# 01_ZYNQ_POWER.net
KiCad netlist of a schematic drawn in Altium Designer
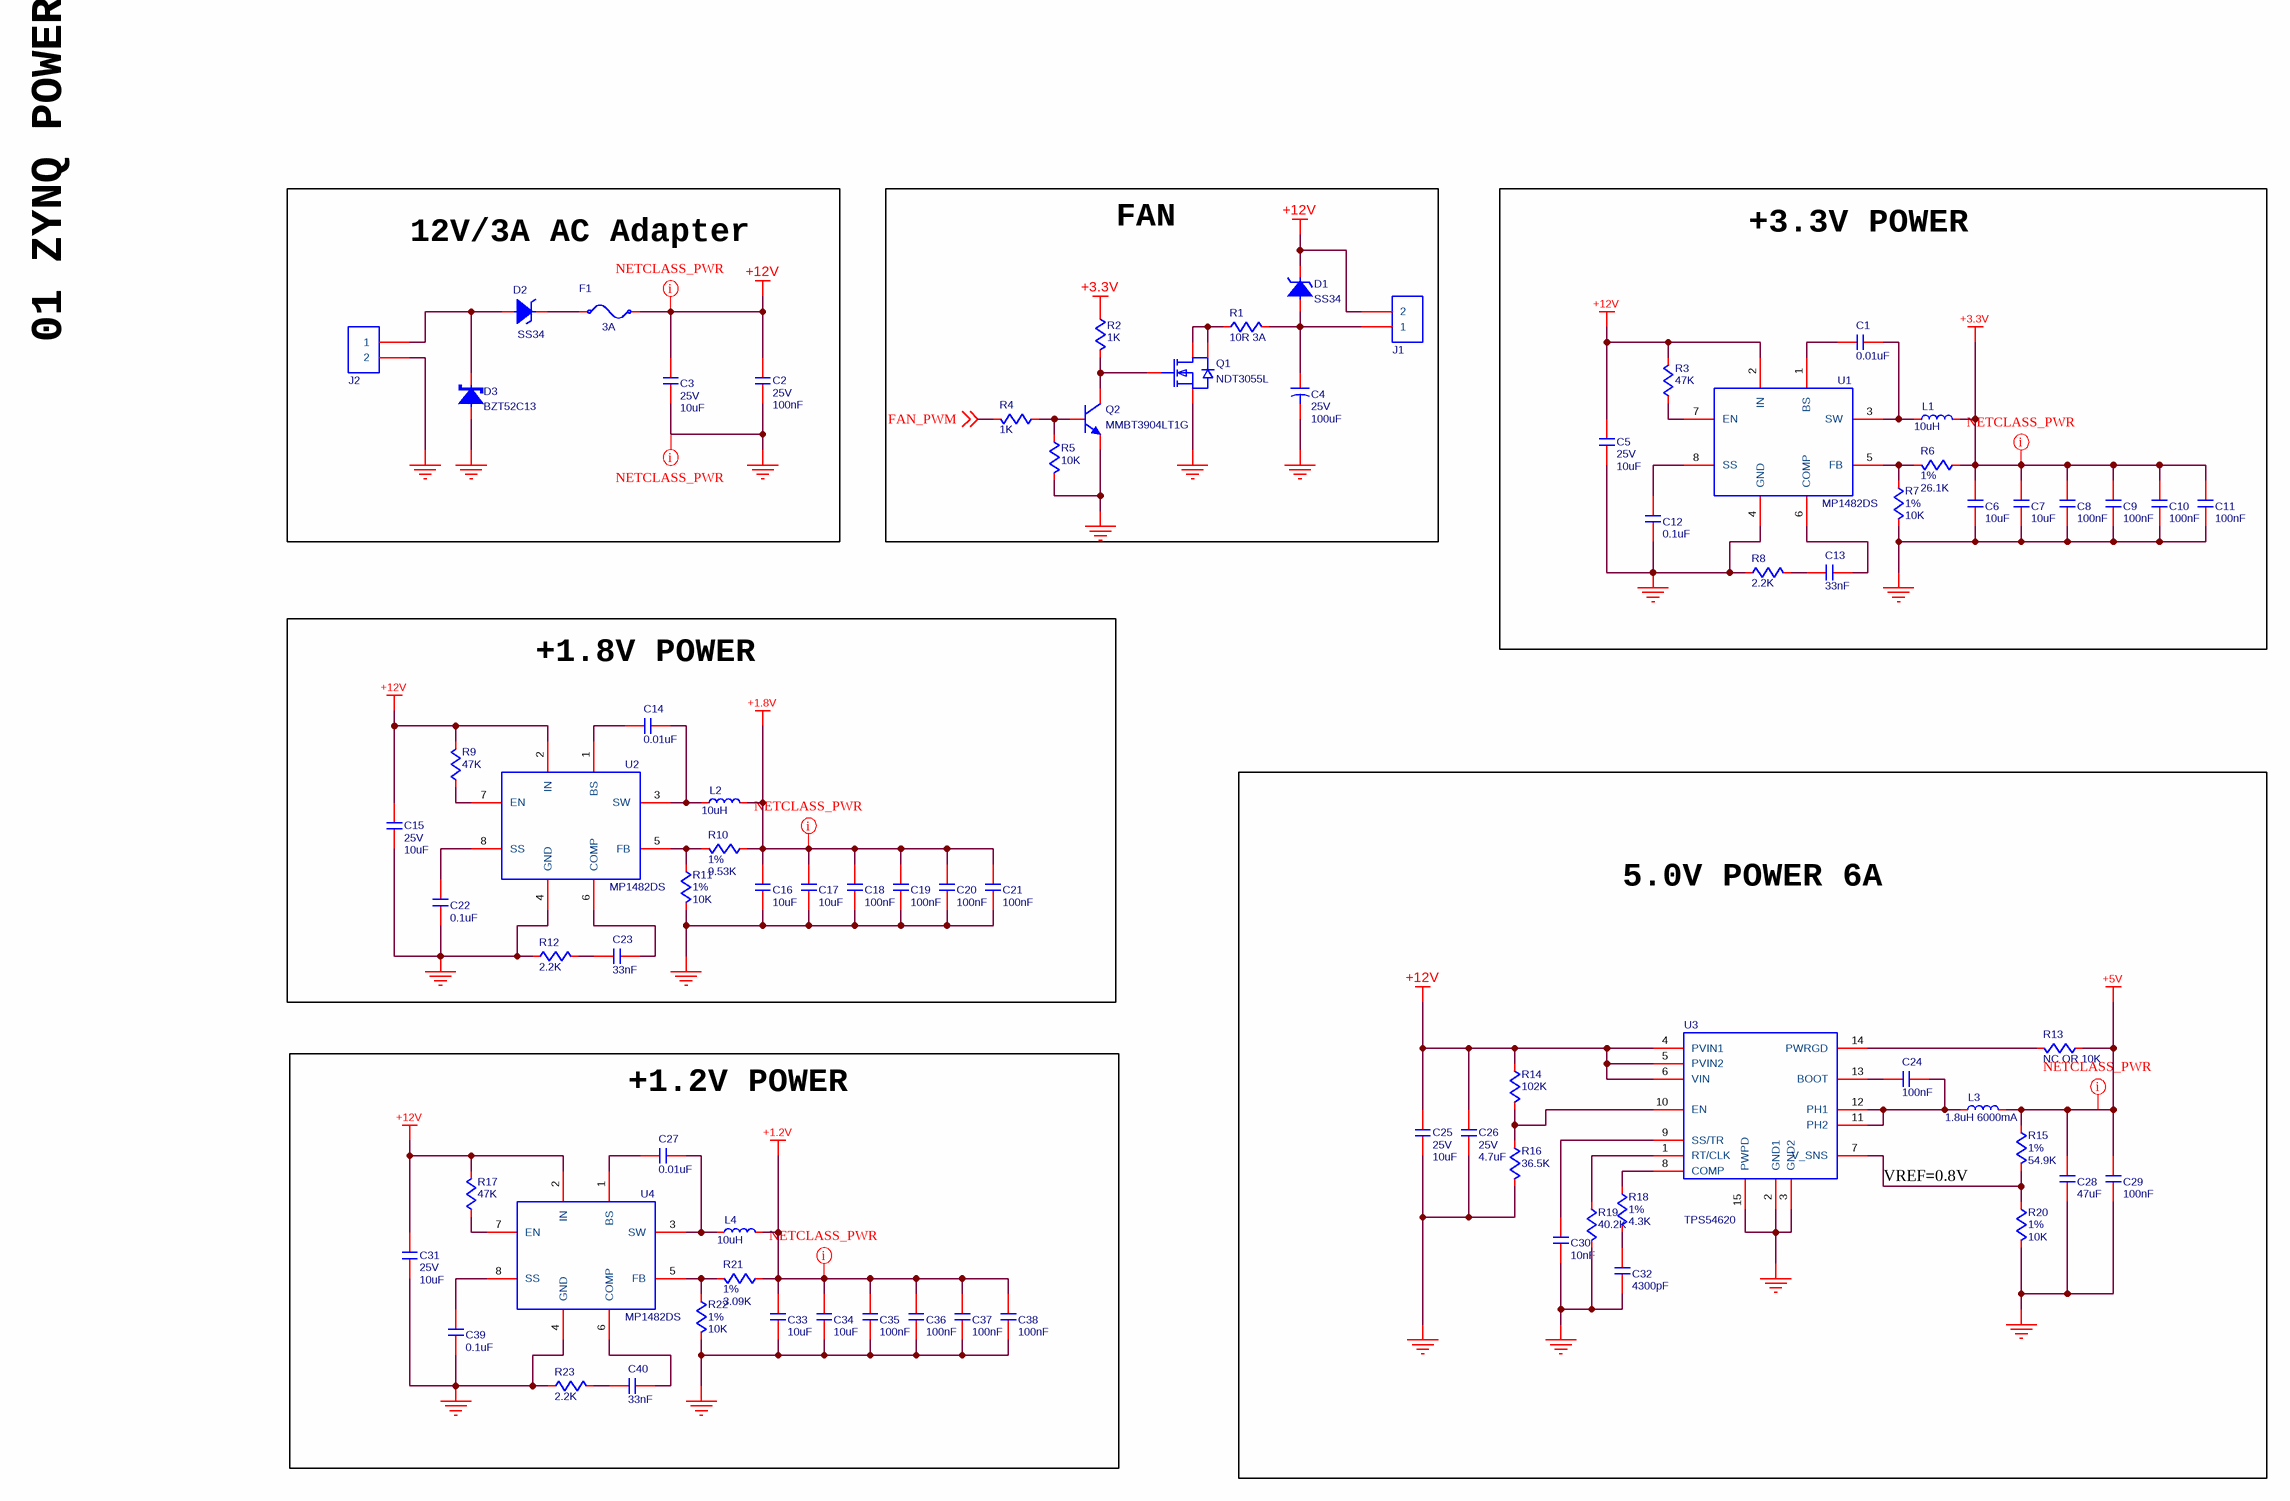
[diagram p0: 01_ZYNQ_POWER.SchDoc]

(export (version "E")
  (design (tool "Eeschema 10.0.6"))
  (components
    (comp (ref "C1")
      (value "0.01uF")
      (footprint "zynq:C0402")
      (fields (field (name "VOLTAGE") "25V") (field (name "Comment") "C-NOMO"))
      (libsource (lib "zynq") (part "C-NOMO"))
    )
    (comp (ref "C2")
      (value "100nF")
      (footprint "zynq:C0402")
      (fields (field (name "VOLTAGE") "25V") (field (name "Comment") "C-NOMO"))
      (libsource (lib "zynq") (part "C-NOMO"))
    )
    (comp (ref "C3")
      (value "10uF")
      (footprint "zynq:C0805")
      (fields (field (name "VOLTAGE") "25V") (field (name "Comment") "C-NOMO"))
      (libsource (lib "zynq") (part "C-NOMO"))
    )
    (comp (ref "C4")
      (value "100uF")
      (footprint "zynq:C7343")
      (fields (field (name "VOLTAGE") "25V") (field (name "Comment") "C-POL"))
      (libsource (lib "zynq") (part "C-POL"))
    )
    (comp (ref "C5")
      (value "10uF")
      (footprint "zynq:C0805")
      (fields (field (name "VOLTAGE") "25V") (field (name "Comment") "C-NOMO"))
      (libsource (lib "zynq") (part "C-NOMO"))
    )
    (comp (ref "C6")
      (value "10uF")
      (footprint "zynq:C0805")
      (fields (field (name "VOLTAGE") "25V") (field (name "Comment") "C-NOMO"))
      (libsource (lib "zynq") (part "C-NOMO"))
    )
    (comp (ref "C7")
      (value "10uF")
      (footprint "zynq:C0805")
      (fields (field (name "VOLTAGE") "25V") (field (name "Comment") "C-NOMO"))
      (libsource (lib "zynq") (part "C-NOMO"))
    )
    (comp (ref "C8")
      (value "100nF")
      (footprint "zynq:C0402")
      (fields (field (name "VOLTAGE") "25V") (field (name "Comment") "C-NOMO"))
      (libsource (lib "zynq") (part "C-NOMO"))
    )
    (comp (ref "C9")
      (value "100nF")
      (footprint "zynq:C0402")
      (fields (field (name "VOLTAGE") "25V") (field (name "Comment") "C-NOMO"))
      (libsource (lib "zynq") (part "C-NOMO"))
    )
    (comp (ref "C10")
      (value "100nF")
      (footprint "zynq:C0402")
      (fields (field (name "VOLTAGE") "25V") (field (name "Comment") "C-NOMO"))
      (libsource (lib "zynq") (part "C-NOMO"))
    )
    (comp (ref "C11")
      (value "100nF")
      (footprint "zynq:C0402")
      (fields (field (name "VOLTAGE") "25V") (field (name "Comment") "C-NOMO"))
      (libsource (lib "zynq") (part "C-NOMO"))
    )
    (comp (ref "C12")
      (value "0.1uF")
      (footprint "zynq:C0402")
      (fields (field (name "VOLTAGE") "25V") (field (name "Comment") "C-NOMO"))
      (libsource (lib "zynq") (part "C-NOMO"))
    )
    (comp (ref "C13")
      (value "33nF")
      (footprint "zynq:C0402")
      (fields (field (name "VOLTAGE") "25V") (field (name "Comment") "C-NOMO"))
      (libsource (lib "zynq") (part "C-NOMO"))
    )
    (comp (ref "C14")
      (value "0.01uF")
      (footprint "zynq:C0402")
      (fields (field (name "VOLTAGE") "25V") (field (name "Comment") "C-NOMO"))
      (libsource (lib "zynq") (part "C-NOMO"))
    )
    (comp (ref "C15")
      (value "10uF")
      (footprint "zynq:C0805")
      (fields (field (name "VOLTAGE") "25V") (field (name "Comment") "C-NOMO"))
      (libsource (lib "zynq") (part "C-NOMO"))
    )
    (comp (ref "C16")
      (value "10uF")
      (footprint "zynq:C0805")
      (fields (field (name "VOLTAGE") "25V") (field (name "Comment") "C-NOMO"))
      (libsource (lib "zynq") (part "C-NOMO"))
    )
    (comp (ref "C17")
      (value "10uF")
      (footprint "zynq:C0805")
      (fields (field (name "VOLTAGE") "25V") (field (name "Comment") "C-NOMO"))
      (libsource (lib "zynq") (part "C-NOMO"))
    )
    (comp (ref "C18")
      (value "100nF")
      (footprint "zynq:C0402")
      (fields (field (name "VOLTAGE") "25V") (field (name "Comment") "C-NOMO"))
      (libsource (lib "zynq") (part "C-NOMO"))
    )
    (comp (ref "C19")
      (value "100nF")
      (footprint "zynq:C0402")
      (fields (field (name "VOLTAGE") "25V") (field (name "Comment") "C-NOMO"))
      (libsource (lib "zynq") (part "C-NOMO"))
    )
    (comp (ref "C20")
      (value "100nF")
      (footprint "zynq:C0402")
      (fields (field (name "VOLTAGE") "25V") (field (name "Comment") "C-NOMO"))
      (libsource (lib "zynq") (part "C-NOMO"))
    )
    (comp (ref "C21")
      (value "100nF")
      (footprint "zynq:C0402")
      (fields (field (name "VOLTAGE") "25V") (field (name "Comment") "C-NOMO"))
      (libsource (lib "zynq") (part "C-NOMO"))
    )
    (comp (ref "C22")
      (value "0.1uF")
      (footprint "zynq:C0402")
      (fields (field (name "VOLTAGE") "25V") (field (name "Comment") "C-NOMO"))
      (libsource (lib "zynq") (part "C-NOMO"))
    )
    (comp (ref "C23")
      (value "33nF")
      (footprint "zynq:C0402")
      (fields (field (name "VOLTAGE") "25V") (field (name "Comment") "C-NOMO"))
      (libsource (lib "zynq") (part "C-NOMO"))
    )
    (comp (ref "C24")
      (value "100nF")
      (footprint "zynq:C0402")
      (fields (field (name "VOLTAGE") "25V") (field (name "Comment") "C-NOMO"))
      (libsource (lib "zynq") (part "C-NOMO"))
    )
    (comp (ref "C25")
      (value "10uF")
      (footprint "zynq:C0805")
      (fields (field (name "VOLTAGE") "25V") (field (name "Comment") "C-NOMO"))
      (libsource (lib "zynq") (part "C-NOMO"))
    )
    (comp (ref "C26")
      (value "4.7uF")
      (footprint "zynq:C0805")
      (fields (field (name "VOLTAGE") "25V") (field (name "Comment") "C-NOMO"))
      (libsource (lib "zynq") (part "C-NOMO"))
    )
    (comp (ref "C27")
      (value "0.01uF")
      (footprint "zynq:C0402")
      (fields (field (name "VOLTAGE") "25V") (field (name "Comment") "C-NOMO"))
      (libsource (lib "zynq") (part "C-NOMO"))
    )
    (comp (ref "C28")
      (value "47uF")
      (footprint "zynq:C0805")
      (fields (field (name "VOLTAGE") "25V") (field (name "Comment") "C-NOMO"))
      (libsource (lib "zynq") (part "C-NOMO"))
    )
    (comp (ref "C29")
      (value "100nF")
      (footprint "zynq:C0402")
      (fields (field (name "VOLTAGE") "25V") (field (name "Comment") "C-NOMO"))
      (libsource (lib "zynq") (part "C-NOMO"))
    )
    (comp (ref "C30")
      (value "10nF")
      (footprint "zynq:C0402")
      (fields (field (name "VOLTAGE") "25V") (field (name "Comment") "C-NOMO"))
      (libsource (lib "zynq") (part "C-NOMO"))
    )
    (comp (ref "C31")
      (value "10uF")
      (footprint "zynq:C0805")
      (fields (field (name "VOLTAGE") "25V") (field (name "Comment") "C-NOMO"))
      (libsource (lib "zynq") (part "C-NOMO"))
    )
    (comp (ref "C32")
      (value "4300pF")
      (footprint "zynq:C0402")
      (fields (field (name "VOLTAGE") "25V") (field (name "Comment") "C-NOMO"))
      (libsource (lib "zynq") (part "C-NOMO"))
    )
    (comp (ref "C33")
      (value "10uF")
      (footprint "zynq:C0805")
      (fields (field (name "VOLTAGE") "25V") (field (name "Comment") "C-NOMO"))
      (libsource (lib "zynq") (part "C-NOMO"))
    )
    (comp (ref "C34")
      (value "10uF")
      (footprint "zynq:C0805")
      (fields (field (name "VOLTAGE") "25V") (field (name "Comment") "C-NOMO"))
      (libsource (lib "zynq") (part "C-NOMO"))
    )
    (comp (ref "C35")
      (value "100nF")
      (footprint "zynq:C0402")
      (fields (field (name "VOLTAGE") "25V") (field (name "Comment") "C-NOMO"))
      (libsource (lib "zynq") (part "C-NOMO"))
    )
    (comp (ref "C36")
      (value "100nF")
      (footprint "zynq:C0402")
      (fields (field (name "VOLTAGE") "25V") (field (name "Comment") "C-NOMO"))
      (libsource (lib "zynq") (part "C-NOMO"))
    )
    (comp (ref "C37")
      (value "100nF")
      (footprint "zynq:C0402")
      (fields (field (name "VOLTAGE") "25V") (field (name "Comment") "C-NOMO"))
      (libsource (lib "zynq") (part "C-NOMO"))
    )
    (comp (ref "C38")
      (value "100nF")
      (footprint "zynq:C0402")
      (fields (field (name "VOLTAGE") "25V") (field (name "Comment") "C-NOMO"))
      (libsource (lib "zynq") (part "C-NOMO"))
    )
    (comp (ref "C39")
      (value "0.1uF")
      (footprint "zynq:C0402")
      (fields (field (name "VOLTAGE") "25V") (field (name "Comment") "C-NOMO"))
      (libsource (lib "zynq") (part "C-NOMO"))
    )
    (comp (ref "C40")
      (value "33nF")
      (footprint "zynq:C0402")
      (fields (field (name "VOLTAGE") "25V") (field (name "Comment") "C-NOMO"))
      (libsource (lib "zynq") (part "C-NOMO"))
    )
    (comp (ref "D1")
      (value "SS34")
      (footprint "zynq:DO-214AC")
      (description "BAS16XV2T1G")
      (libsource (lib "zynq") (part "DIOD2"))
    )
    (comp (ref "D2")
      (value "SS34")
      (footprint "zynq:DO-214AC")
      (description "BAS16XV2T1G")
      (libsource (lib "zynq") (part "DIOD2"))
    )
    (comp (ref "D3") (value "BZT52C13") (footprint "zynq:DO-214AC") (libsource (lib "zynq") (part "DIOD3")))
    (comp (ref "F1") (value "3A") (footprint "zynq:F1812") (libsource (lib "zynq") (part "FUSE")))
    (comp (ref "J1") (value "HDR1X2") (footprint "zynq:XH-2A") (libsource (lib "") (part "HDR1X2_1")))
    (comp (ref "J2")
      (value "HDR1X2")
      (footprint "zynq:KF301-5.0-2P")
      (libsource (lib "zynq") (part "HDR1X2"))
    )
    (comp (ref "L1")
      (value "10uH")
      (footprint "zynq:FXL0624")
      (fields (field (name "Comment") "L") (field (name "PUBLISHER") "Altium Limited"))
      (libsource (lib "zynq") (part "L"))
    )
    (comp (ref "L2")
      (value "10uH")
      (footprint "zynq:FXL0624")
      (fields (field (name "Comment") "L") (field (name "PUBLISHER") "Altium Limited"))
      (libsource (lib "zynq") (part "L"))
    )
    (comp (ref "L3")
      (value "1.8uH 6000mA")
      (footprint "zynq:FXL0624")
      (fields (field (name "Comment") "L") (field (name "PUBLISHER") "Altium Limited"))
      (libsource (lib "zynq") (part "L"))
    )
    (comp (ref "L4")
      (value "10uH")
      (footprint "zynq:FXL0624")
      (fields (field (name "Comment") "L") (field (name "PUBLISHER") "Altium Limited"))
      (libsource (lib "zynq") (part "L"))
    )
    (comp (ref "Q1") (value "NDT3055L") (footprint "zynq:SOT-223") (libsource (lib "zynq") (part "NDT3055L")))
    (comp (ref "Q2") (value "MMBT3904LT1G") (footprint "zynq:SOT-23") (libsource (lib "zynq") (part "NPN")))
    (comp (ref "R1")
      (value "10R 3A")
      (footprint "zynq:R1812")
      (fields (field (name "Comment") "R"))
      (libsource (lib "zynq") (part "R"))
    )
    (comp (ref "R2")
      (value "1K")
      (footprint "zynq:R0402")
      (fields (field (name "Comment") "R"))
      (libsource (lib "zynq") (part "R"))
    )
    (comp (ref "R3")
      (value "47K")
      (footprint "zynq:R0402")
      (fields (field (name "Comment") "R"))
      (libsource (lib "zynq") (part "R"))
    )
    (comp (ref "R4")
      (value "1K")
      (footprint "zynq:R0402")
      (fields (field (name "Comment") "R"))
      (libsource (lib "zynq") (part "R"))
    )
    (comp (ref "R5")
      (value "10K")
      (footprint "zynq:R0402")
      (fields (field (name "Comment") "R"))
      (libsource (lib "zynq") (part "R"))
    )
    (comp (ref "R6")
      (value "26.1K")
      (footprint "zynq:R0402")
      (fields (field (name "PRECISION") "1%") (field (name "Comment") "R"))
      (libsource (lib "zynq") (part "R"))
    )
    (comp (ref "R7")
      (value "10K")
      (footprint "zynq:R0402")
      (fields (field (name "PRECISION") "1%") (field (name "Comment") "R"))
      (libsource (lib "zynq") (part "R"))
    )
    (comp (ref "R8")
      (value "2.2K")
      (footprint "zynq:R0402")
      (fields (field (name "Comment") "R"))
      (libsource (lib "zynq") (part "R"))
    )
    (comp (ref "R9")
      (value "47K")
      (footprint "zynq:R0402")
      (fields (field (name "Comment") "R"))
      (libsource (lib "zynq") (part "R"))
    )
    (comp (ref "R10")
      (value "9.53K")
      (footprint "zynq:R0402")
      (fields (field (name "PRECISION") "1%") (field (name "Comment") "R"))
      (libsource (lib "zynq") (part "R"))
    )
    (comp (ref "R11")
      (value "10K")
      (footprint "zynq:R0402")
      (fields (field (name "PRECISION") "1%") (field (name "Comment") "R"))
      (libsource (lib "zynq") (part "R"))
    )
    (comp (ref "R12")
      (value "2.2K")
      (footprint "zynq:R0402")
      (fields (field (name "Comment") "R"))
      (libsource (lib "zynq") (part "R"))
    )
    (comp (ref "R13")
      (value "NC OR 10K")
      (footprint "zynq:R0402")
      (fields (field (name "Comment") "R"))
      (libsource (lib "zynq") (part "R"))
    )
    (comp (ref "R14")
      (value "102K")
      (footprint "zynq:R0402")
      (fields (field (name "Comment") "R"))
      (libsource (lib "zynq") (part "R"))
    )
    (comp (ref "R15")
      (value "54.9K")
      (footprint "zynq:R0603")
      (fields (field (name "PRECISION") "1%") (field (name "Comment") "R"))
      (libsource (lib "zynq") (part "R"))
    )
    (comp (ref "R16")
      (value "36.5K")
      (footprint "zynq:R0402")
      (fields (field (name "Comment") "R"))
      (libsource (lib "zynq") (part "R"))
    )
    (comp (ref "R17")
      (value "47K")
      (footprint "zynq:R0402")
      (fields (field (name "Comment") "R"))
      (libsource (lib "zynq") (part "R"))
    )
    (comp (ref "R18")
      (value "4.3K")
      (footprint "zynq:R0402")
      (fields (field (name "PRECISION") "1%") (field (name "Comment") "R"))
      (libsource (lib "zynq") (part "R"))
    )
    (comp (ref "R19")
      (value "40.2K")
      (footprint "zynq:R0402")
      (fields (field (name "Comment") "R"))
      (libsource (lib "zynq") (part "R"))
    )
    (comp (ref "R20")
      (value "10K")
      (footprint "zynq:R0603")
      (fields (field (name "PRECISION") "1%") (field (name "Comment") "R"))
      (libsource (lib "zynq") (part "R"))
    )
    (comp (ref "R21")
      (value "3.09K")
      (footprint "zynq:R0402")
      (fields (field (name "PRECISION") "1%") (field (name "Comment") "R"))
      (libsource (lib "zynq") (part "R"))
    )
    (comp (ref "R22")
      (value "10K")
      (footprint "zynq:R0402")
      (fields (field (name "PRECISION") "1%") (field (name "Comment") "R"))
      (libsource (lib "zynq") (part "R"))
    )
    (comp (ref "R23")
      (value "2.2K")
      (footprint "zynq:R0402")
      (fields (field (name "Comment") "R"))
      (libsource (lib "zynq") (part "R"))
    )
    (comp (ref "U1") (value "MP1482DS") (footprint "zynq:MP1482") (libsource (lib "zynq") (part "MP1482DS")))
    (comp (ref "U2") (value "MP1482DS") (footprint "zynq:MP1482") (libsource (lib "zynq") (part "MP1482DS")))
    (comp (ref "U3")
      (value "TPS54620")
      (footprint "zynq:TPS54620")
      (libsource (lib "zynq") (part "TPS54620"))
    )
    (comp (ref "U4") (value "MP1482DS") (footprint "zynq:MP1482") (libsource (lib "zynq") (part "MP1482DS")))
  )
  (nets
    (net (code "1") (name "+1.2V") (class "Default")
      (node (ref "C33") (pin "2") (pinfunction "2_2") (pintype "passive"))
      (node (ref "C34") (pin "2") (pinfunction "2_2") (pintype "passive"))
      (node (ref "C35") (pin "2") (pinfunction "2_2") (pintype "passive"))
      (node (ref "C36") (pin "2") (pinfunction "2_2") (pintype "passive"))
      (node (ref "C37") (pin "2") (pinfunction "2_2") (pintype "passive"))
      (node (ref "C38") (pin "2") (pinfunction "2_2") (pintype "passive"))
      (node (ref "L4") (pin "2") (pinfunction "2_2") (pintype "passive"))
      (node (ref "R21") (pin "2") (pinfunction "2_2") (pintype "passive"))
    )
    (net (code "2") (name "+1.8V") (class "Default")
      (node (ref "C16") (pin "2") (pinfunction "2_2") (pintype "passive"))
      (node (ref "C17") (pin "2") (pinfunction "2_2") (pintype "passive"))
      (node (ref "C18") (pin "2") (pinfunction "2_2") (pintype "passive"))
      (node (ref "C19") (pin "2") (pinfunction "2_2") (pintype "passive"))
      (node (ref "C20") (pin "2") (pinfunction "2_2") (pintype "passive"))
      (node (ref "C21") (pin "2") (pinfunction "2_2") (pintype "passive"))
      (node (ref "L2") (pin "2") (pinfunction "2_2") (pintype "passive"))
      (node (ref "R10") (pin "2") (pinfunction "2_2") (pintype "passive"))
    )
    (net (code "3") (name "+3.3V") (class "Default")
      (node (ref "C10") (pin "2") (pinfunction "2_2") (pintype "passive"))
      (node (ref "C11") (pin "2") (pinfunction "2_2") (pintype "passive"))
      (node (ref "C6") (pin "2") (pinfunction "2_2") (pintype "passive"))
      (node (ref "C7") (pin "2") (pinfunction "2_2") (pintype "passive"))
      (node (ref "C8") (pin "2") (pinfunction "2_2") (pintype "passive"))
      (node (ref "C9") (pin "2") (pinfunction "2_2") (pintype "passive"))
      (node (ref "L1") (pin "2") (pinfunction "2_2") (pintype "passive"))
      (node (ref "R2") (pin "2") (pinfunction "2_2") (pintype "passive"))
      (node (ref "R6") (pin "2") (pinfunction "2_2") (pintype "passive"))
    )
    (net (code "4") (name "+5V") (class "Default")
      (node (ref "C28") (pin "1") (pinfunction "1_1") (pintype "passive"))
      (node (ref "C29") (pin "1") (pinfunction "1_1") (pintype "passive"))
      (node (ref "L3") (pin "2") (pinfunction "2_2") (pintype "passive"))
      (node (ref "R13") (pin "2") (pinfunction "2_2") (pintype "passive"))
      (node (ref "R15") (pin "2") (pinfunction "2_2") (pintype "passive"))
    )
    (net (code "5") (name "+12V") (class "Default")
      (node (ref "C15") (pin "2") (pinfunction "2_2") (pintype "passive"))
      (node (ref "C2") (pin "2") (pinfunction "2_2") (pintype "passive"))
      (node (ref "C25") (pin "2") (pinfunction "2_2") (pintype "passive"))
      (node (ref "C26") (pin "2") (pinfunction "2_2") (pintype "passive"))
      (node (ref "C3") (pin "2") (pinfunction "2_2") (pintype "passive"))
      (node (ref "C31") (pin "2") (pinfunction "2_2") (pintype "passive"))
      (node (ref "C5") (pin "2") (pinfunction "2_2") (pintype "passive"))
      (node (ref "D1") (pin "1") (pinfunction "1_1") (pintype "passive"))
      (node (ref "F1") (pin "2") (pinfunction "2_2") (pintype "passive"))
      (node (ref "J1") (pin "2") (pinfunction "2_2") (pintype "passive"))
      (node (ref "R14") (pin "2") (pinfunction "2_2") (pintype "passive"))
      (node (ref "R17") (pin "1") (pinfunction "1_1") (pintype "passive"))
      (node (ref "R3") (pin "1") (pinfunction "1_1") (pintype "passive"))
      (node (ref "R9") (pin "1") (pinfunction "1_1") (pintype "passive"))
      (node (ref "U1") (pin "2") (pinfunction "IN_2") (pintype "passive"))
      (node (ref "U2") (pin "2") (pinfunction "IN_2") (pintype "passive"))
      (node (ref "U3") (pin "4") (pinfunction "PVIN1_4") (pintype "passive"))
      (node (ref "U3") (pin "5") (pinfunction "PVIN2_5") (pintype "passive"))
      (node (ref "U3") (pin "6") (pinfunction "VIN_6") (pintype "passive"))
      (node (ref "U4") (pin "2") (pinfunction "IN_2") (pintype "passive"))
    )
    (net (code "6") (name "FAN_PWM") (class "Default")
      (node (ref "R4") (pin "1") (pinfunction "1_1") (pintype "passive"))
    )
    (net (code "7") (name "GND") (class "Default")
      (node (ref "C10") (pin "1") (pinfunction "1_1") (pintype "passive"))
      (node (ref "C11") (pin "1") (pinfunction "1_1") (pintype "passive"))
      (node (ref "C12") (pin "1") (pinfunction "1_1") (pintype "passive"))
      (node (ref "C15") (pin "1") (pinfunction "1_1") (pintype "passive"))
      (node (ref "C16") (pin "1") (pinfunction "1_1") (pintype "passive"))
      (node (ref "C17") (pin "1") (pinfunction "1_1") (pintype "passive"))
      (node (ref "C18") (pin "1") (pinfunction "1_1") (pintype "passive"))
      (node (ref "C19") (pin "1") (pinfunction "1_1") (pintype "passive"))
      (node (ref "C2") (pin "1") (pinfunction "1_1") (pintype "passive"))
      (node (ref "C20") (pin "1") (pinfunction "1_1") (pintype "passive"))
      (node (ref "C21") (pin "1") (pinfunction "1_1") (pintype "passive"))
      (node (ref "C22") (pin "1") (pinfunction "1_1") (pintype "passive"))
      (node (ref "C25") (pin "1") (pinfunction "1_1") (pintype "passive"))
      (node (ref "C26") (pin "1") (pinfunction "1_1") (pintype "passive"))
      (node (ref "C28") (pin "2") (pinfunction "2_2") (pintype "passive"))
      (node (ref "C29") (pin "2") (pinfunction "2_2") (pintype "passive"))
      (node (ref "C3") (pin "1") (pinfunction "1_1") (pintype "passive"))
      (node (ref "C30") (pin "1") (pinfunction "1_1") (pintype "passive"))
      (node (ref "C31") (pin "1") (pinfunction "1_1") (pintype "passive"))
      (node (ref "C32") (pin "1") (pinfunction "1_1") (pintype "passive"))
      (node (ref "C33") (pin "1") (pinfunction "1_1") (pintype "passive"))
      (node (ref "C34") (pin "1") (pinfunction "1_1") (pintype "passive"))
      (node (ref "C35") (pin "1") (pinfunction "1_1") (pintype "passive"))
      (node (ref "C36") (pin "1") (pinfunction "1_1") (pintype "passive"))
      (node (ref "C37") (pin "1") (pinfunction "1_1") (pintype "passive"))
      (node (ref "C38") (pin "1") (pinfunction "1_1") (pintype "passive"))
      (node (ref "C39") (pin "1") (pinfunction "1_1") (pintype "passive"))
      (node (ref "C4") (pin "2") (pinfunction "2_2") (pintype "passive"))
      (node (ref "C5") (pin "1") (pinfunction "1_1") (pintype "passive"))
      (node (ref "C6") (pin "1") (pinfunction "1_1") (pintype "passive"))
      (node (ref "C7") (pin "1") (pinfunction "1_1") (pintype "passive"))
      (node (ref "C8") (pin "1") (pinfunction "1_1") (pintype "passive"))
      (node (ref "C9") (pin "1") (pinfunction "1_1") (pintype "passive"))
      (node (ref "D3") (pin "2") (pinfunction "2_2") (pintype "passive"))
      (node (ref "J2") (pin "2") (pinfunction "2_2") (pintype "passive"))
      (node (ref "Q1") (pin "3") (pinfunction "S_3") (pintype "passive"))
      (node (ref "Q2") (pin "2") (pinfunction "E_2") (pintype "passive"))
      (node (ref "R11") (pin "1") (pinfunction "1_1") (pintype "passive"))
      (node (ref "R12") (pin "2") (pinfunction "2_2") (pintype "passive"))
      (node (ref "R16") (pin "1") (pinfunction "1_1") (pintype "passive"))
      (node (ref "R19") (pin "1") (pinfunction "1_1") (pintype "passive"))
      (node (ref "R20") (pin "1") (pinfunction "1_1") (pintype "passive"))
      (node (ref "R22") (pin "1") (pinfunction "1_1") (pintype "passive"))
      (node (ref "R23") (pin "2") (pinfunction "2_2") (pintype "passive"))
      (node (ref "R5") (pin "1") (pinfunction "1_1") (pintype "passive"))
      (node (ref "R7") (pin "1") (pinfunction "1_1") (pintype "passive"))
      (node (ref "R8") (pin "2") (pinfunction "2_2") (pintype "passive"))
      (node (ref "U1") (pin "4") (pinfunction "GND_4") (pintype "passive"))
      (node (ref "U2") (pin "4") (pinfunction "GND_4") (pintype "passive"))
      (node (ref "U3") (pin "15") (pinfunction "PWPD_15") (pintype "passive"))
      (node (ref "U3") (pin "2") (pinfunction "GND1_2") (pintype "passive"))
      (node (ref "U3") (pin "3") (pinfunction "GND2_3") (pintype "passive"))
      (node (ref "U4") (pin "4") (pinfunction "GND_4") (pintype "passive"))
    )
    (net (code "8") (name "Net-(C4-Pad1)") (class "Default")
      (node (ref "C4") (pin "1") (pinfunction "1_1") (pintype "passive"))
      (node (ref "D1") (pin "2") (pinfunction "2_2") (pintype "passive"))
      (node (ref "J1") (pin "1") (pinfunction "1_1") (pintype "passive"))
      (node (ref "R1") (pin "1") (pinfunction "1_1") (pintype "passive"))
    )
    (net (code "9") (name "Net-(C13-Pad2)") (class "Default")
      (node (ref "C13") (pin "2") (pinfunction "2_2") (pintype "passive"))
      (node (ref "R8") (pin "1") (pinfunction "1_1") (pintype "passive"))
    )
    (net (code "10") (name "Net-(C23-Pad2)") (class "Default")
      (node (ref "C23") (pin "2") (pinfunction "2_2") (pintype "passive"))
      (node (ref "R12") (pin "1") (pinfunction "1_1") (pintype "passive"))
    )
    (net (code "11") (name "Net-(C32-Pad2)") (class "Default")
      (node (ref "C32") (pin "2") (pinfunction "2_2") (pintype "passive"))
      (node (ref "R18") (pin "1") (pinfunction "1_1") (pintype "passive"))
    )
    (net (code "12") (name "Net-(C40-Pad2)") (class "Default")
      (node (ref "C40") (pin "2") (pinfunction "2_2") (pintype "passive"))
      (node (ref "R23") (pin "1") (pinfunction "1_1") (pintype "passive"))
    )
    (net (code "13") (name "Net-(D2-Pad1)") (class "Default")
      (node (ref "D2") (pin "1") (pinfunction "1_1") (pintype "passive"))
      (node (ref "F1") (pin "1") (pinfunction "1_1") (pintype "passive"))
    )
    (net (code "14") (name "Net-(D2-Pad2)") (class "Default")
      (node (ref "D2") (pin "2") (pinfunction "2_2") (pintype "passive"))
      (node (ref "D3") (pin "1") (pinfunction "1_1") (pintype "passive"))
      (node (ref "J2") (pin "1") (pinfunction "1_1") (pintype "passive"))
    )
    (net (code "15") (name "Net-(Q1-D-Pad2)") (class "Default")
      (node (ref "Q1") (pin "2") (pinfunction "D_2") (pintype "passive"))
      (node (ref "Q1") (pin "4") (pinfunction "D_4") (pintype "passive"))
      (node (ref "R1") (pin "2") (pinfunction "2_2") (pintype "passive"))
    )
    (net (code "16") (name "Net-(Q1-G)") (class "Default")
      (node (ref "Q1") (pin "1") (pinfunction "G_1") (pintype "passive"))
      (node (ref "Q2") (pin "3") (pinfunction "C_3") (pintype "passive"))
      (node (ref "R2") (pin "1") (pinfunction "1_1") (pintype "passive"))
    )
    (net (code "17") (name "Net-(Q2-B)") (class "Default")
      (node (ref "Q2") (pin "1") (pinfunction "B_1") (pintype "passive"))
      (node (ref "R4") (pin "2") (pinfunction "2_2") (pintype "passive"))
      (node (ref "R5") (pin "2") (pinfunction "2_2") (pintype "passive"))
    )
    (net (code "18") (name "Net-(U1-BS)") (class "Default")
      (node (ref "C1") (pin "2") (pinfunction "2_2") (pintype "passive"))
      (node (ref "U1") (pin "1") (pinfunction "BS_1") (pintype "passive"))
    )
    (net (code "19") (name "Net-(U1-COMP)") (class "Default")
      (node (ref "C13") (pin "1") (pinfunction "1_1") (pintype "passive"))
      (node (ref "U1") (pin "6") (pinfunction "COMP_6") (pintype "passive"))
    )
    (net (code "20") (name "Net-(U1-EN)") (class "Default")
      (node (ref "R3") (pin "2") (pinfunction "2_2") (pintype "passive"))
      (node (ref "U1") (pin "7") (pinfunction "EN_7") (pintype "passive"))
    )
    (net (code "21") (name "Net-(U1-FB)") (class "Default")
      (node (ref "R6") (pin "1") (pinfunction "1_1") (pintype "passive"))
      (node (ref "R7") (pin "2") (pinfunction "2_2") (pintype "passive"))
      (node (ref "U1") (pin "5") (pinfunction "FB_5") (pintype "passive"))
    )
    (net (code "22") (name "Net-(U1-SS)") (class "Default")
      (node (ref "C12") (pin "2") (pinfunction "2_2") (pintype "passive"))
      (node (ref "U1") (pin "8") (pinfunction "SS_8") (pintype "passive"))
    )
    (net (code "23") (name "Net-(U1-SW)") (class "Default")
      (node (ref "C1") (pin "1") (pinfunction "1_1") (pintype "passive"))
      (node (ref "L1") (pin "1") (pinfunction "1_1") (pintype "passive"))
      (node (ref "U1") (pin "3") (pinfunction "SW_3") (pintype "passive"))
    )
    (net (code "24") (name "Net-(U2-BS)") (class "Default")
      (node (ref "C14") (pin "2") (pinfunction "2_2") (pintype "passive"))
      (node (ref "U2") (pin "1") (pinfunction "BS_1") (pintype "passive"))
    )
    (net (code "25") (name "Net-(U2-COMP)") (class "Default")
      (node (ref "C23") (pin "1") (pinfunction "1_1") (pintype "passive"))
      (node (ref "U2") (pin "6") (pinfunction "COMP_6") (pintype "passive"))
    )
    (net (code "26") (name "Net-(U2-EN)") (class "Default")
      (node (ref "R9") (pin "2") (pinfunction "2_2") (pintype "passive"))
      (node (ref "U2") (pin "7") (pinfunction "EN_7") (pintype "passive"))
    )
    (net (code "27") (name "Net-(U2-FB)") (class "Default")
      (node (ref "R10") (pin "1") (pinfunction "1_1") (pintype "passive"))
      (node (ref "R11") (pin "2") (pinfunction "2_2") (pintype "passive"))
      (node (ref "U2") (pin "5") (pinfunction "FB_5") (pintype "passive"))
    )
    (net (code "28") (name "Net-(U2-SS)") (class "Default")
      (node (ref "C22") (pin "2") (pinfunction "2_2") (pintype "passive"))
      (node (ref "U2") (pin "8") (pinfunction "SS_8") (pintype "passive"))
    )
    (net (code "29") (name "Net-(U2-SW)") (class "Default")
      (node (ref "C14") (pin "1") (pinfunction "1_1") (pintype "passive"))
      (node (ref "L2") (pin "1") (pinfunction "1_1") (pintype "passive"))
      (node (ref "U2") (pin "3") (pinfunction "SW_3") (pintype "passive"))
    )
    (net (code "30") (name "Net-(U3-BOOT)") (class "Default")
      (node (ref "C24") (pin "2") (pinfunction "2_2") (pintype "passive"))
      (node (ref "U3") (pin "13") (pinfunction "BOOT_13") (pintype "passive"))
    )
    (net (code "31") (name "Net-(U3-COMP)") (class "Default")
      (node (ref "R18") (pin "2") (pinfunction "2_2") (pintype "passive"))
      (node (ref "U3") (pin "8") (pinfunction "COMP_8") (pintype "passive"))
    )
    (net (code "32") (name "Net-(U3-EN)") (class "Default")
      (node (ref "R14") (pin "1") (pinfunction "1_1") (pintype "passive"))
      (node (ref "R16") (pin "2") (pinfunction "2_2") (pintype "passive"))
      (node (ref "U3") (pin "10") (pinfunction "EN_10") (pintype "passive"))
    )
    (net (code "33") (name "Net-(U3-PH1)") (class "Default")
      (node (ref "C24") (pin "1") (pinfunction "1_1") (pintype "passive"))
      (node (ref "L3") (pin "1") (pinfunction "1_1") (pintype "passive"))
      (node (ref "U3") (pin "11") (pinfunction "PH2_11") (pintype "passive"))
      (node (ref "U3") (pin "12") (pinfunction "PH1_12") (pintype "passive"))
    )
    (net (code "34") (name "Net-(U3-PWRGD)") (class "Default")
      (node (ref "R13") (pin "1") (pinfunction "1_1") (pintype "passive"))
      (node (ref "U3") (pin "14") (pinfunction "PWRGD_14") (pintype "passive"))
    )
    (net (code "35") (name "Net-(U3-RT{slash}CLK)") (class "Default")
      (node (ref "R19") (pin "2") (pinfunction "2_2") (pintype "passive"))
      (node (ref "U3") (pin "1") (pinfunction "RT/CLK_1") (pintype "passive"))
    )
    (net (code "36") (name "Net-(U3-SS{slash}TR)") (class "Default")
      (node (ref "C30") (pin "2") (pinfunction "2_2") (pintype "passive"))
      (node (ref "U3") (pin "9") (pinfunction "SS/TR_9") (pintype "passive"))
    )
    (net (code "37") (name "Net-(U3-V_SNS)") (class "Default")
      (node (ref "R15") (pin "1") (pinfunction "1_1") (pintype "passive"))
      (node (ref "R20") (pin "2") (pinfunction "2_2") (pintype "passive"))
      (node (ref "U3") (pin "7") (pinfunction "V_SNS_7") (pintype "passive"))
    )
    (net (code "38") (name "Net-(U4-BS)") (class "Default")
      (node (ref "C27") (pin "2") (pinfunction "2_2") (pintype "passive"))
      (node (ref "U4") (pin "1") (pinfunction "BS_1") (pintype "passive"))
    )
    (net (code "39") (name "Net-(U4-COMP)") (class "Default")
      (node (ref "C40") (pin "1") (pinfunction "1_1") (pintype "passive"))
      (node (ref "U4") (pin "6") (pinfunction "COMP_6") (pintype "passive"))
    )
    (net (code "40") (name "Net-(U4-EN)") (class "Default")
      (node (ref "R17") (pin "2") (pinfunction "2_2") (pintype "passive"))
      (node (ref "U4") (pin "7") (pinfunction "EN_7") (pintype "passive"))
    )
    (net (code "41") (name "Net-(U4-FB)") (class "Default")
      (node (ref "R21") (pin "1") (pinfunction "1_1") (pintype "passive"))
      (node (ref "R22") (pin "2") (pinfunction "2_2") (pintype "passive"))
      (node (ref "U4") (pin "5") (pinfunction "FB_5") (pintype "passive"))
    )
    (net (code "42") (name "Net-(U4-SS)") (class "Default")
      (node (ref "C39") (pin "2") (pinfunction "2_2") (pintype "passive"))
      (node (ref "U4") (pin "8") (pinfunction "SS_8") (pintype "passive"))
    )
    (net (code "43") (name "Net-(U4-SW)") (class "Default")
      (node (ref "C27") (pin "1") (pinfunction "1_1") (pintype "passive"))
      (node (ref "L4") (pin "1") (pinfunction "1_1") (pintype "passive"))
      (node (ref "U4") (pin "3") (pinfunction "SW_3") (pintype "passive"))
    )
  )
)
